# VCO-Simple-Middle.net
KiCad netlist of a schematic drawn in EAGLE
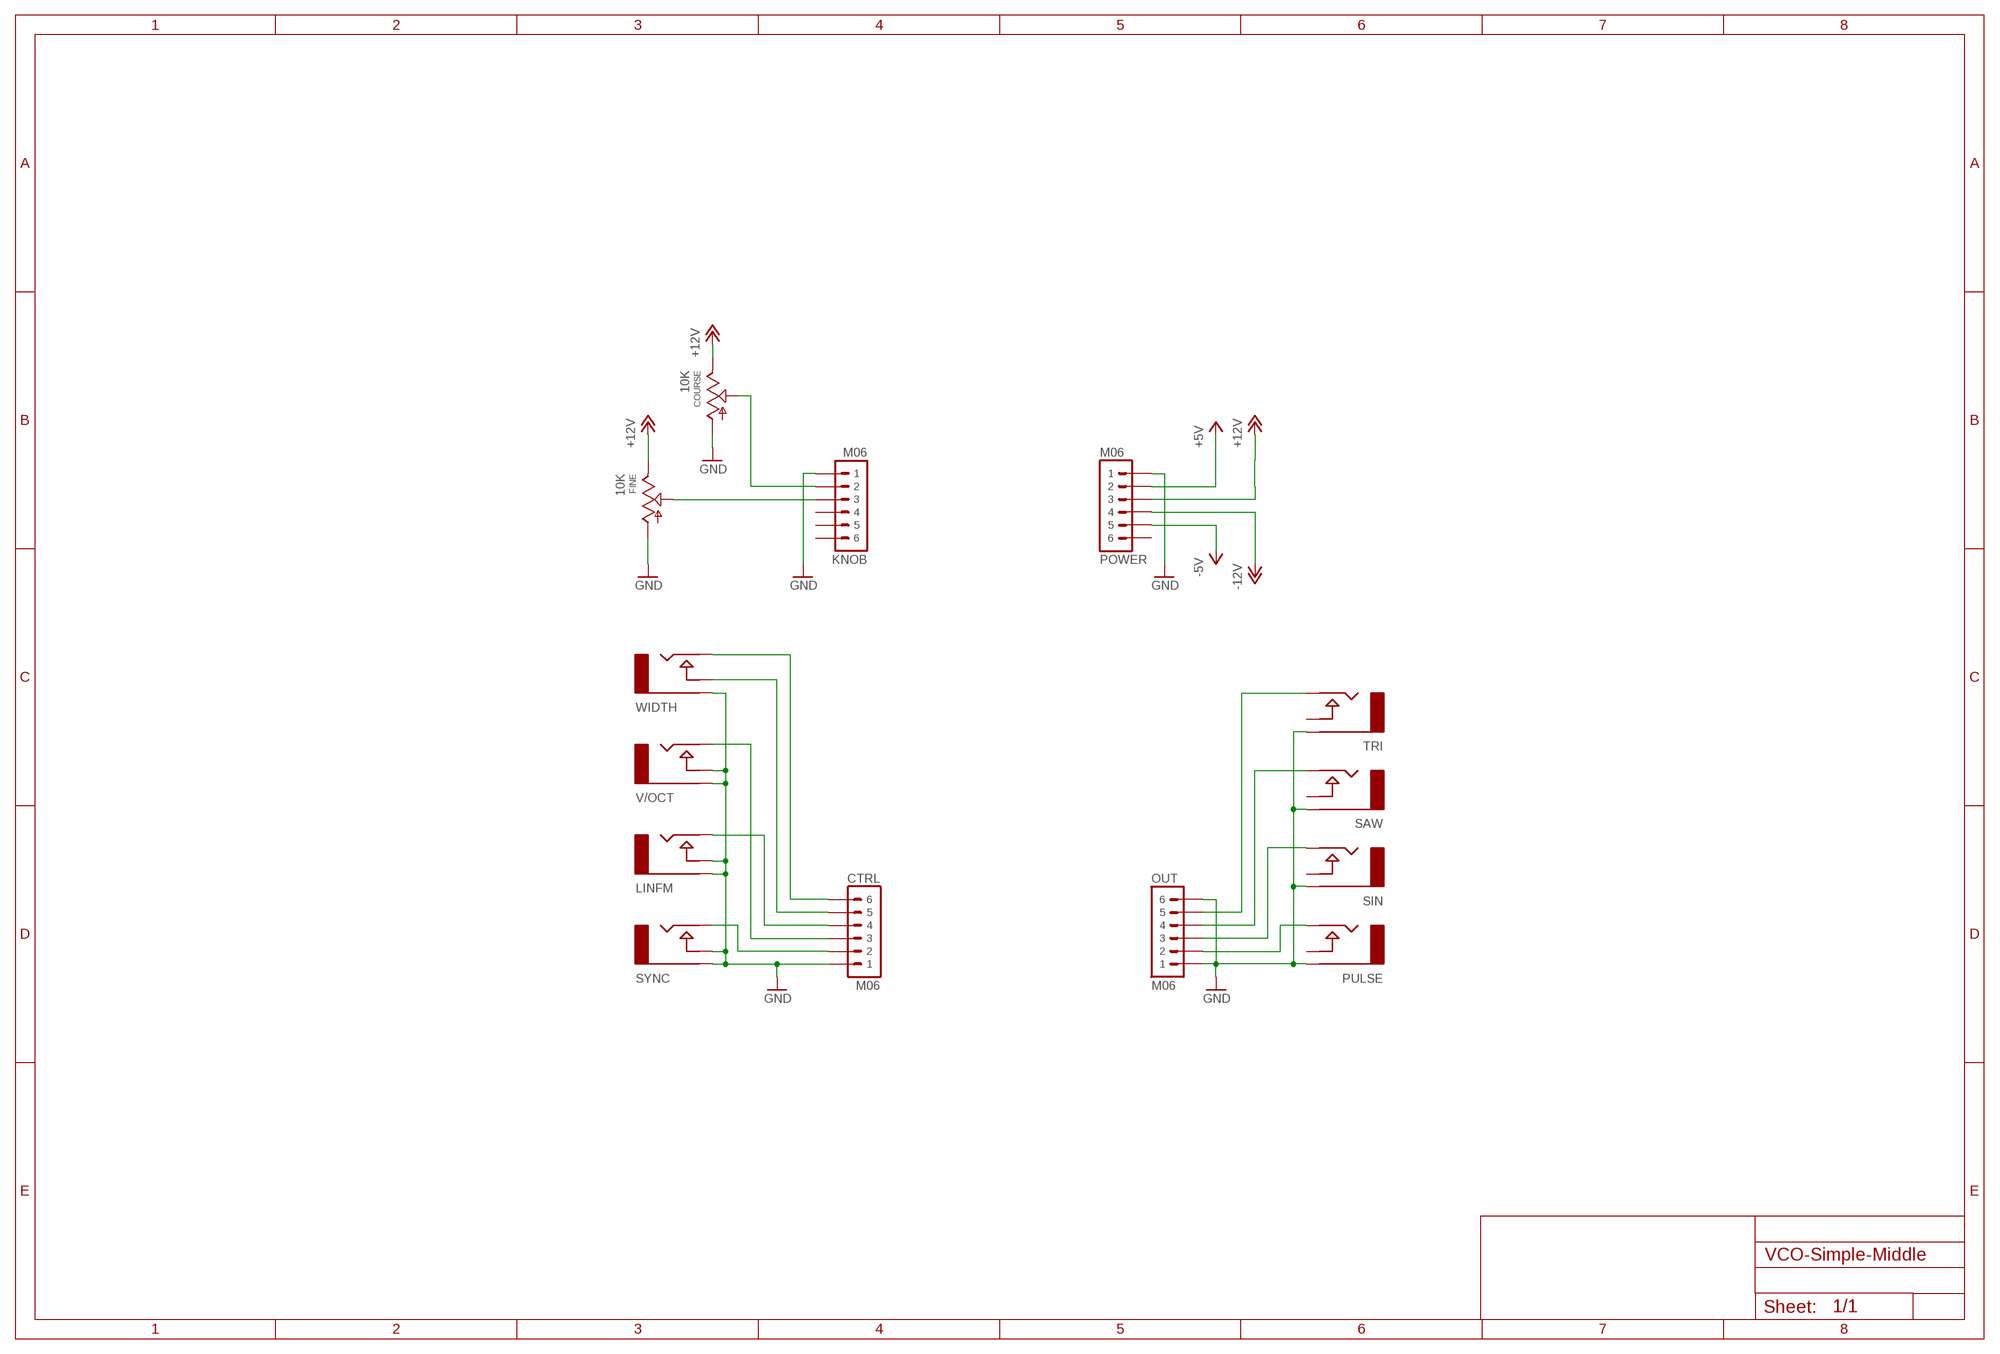
[diagram p0: schematic, sheet 1]

(export (version "E")
  (design (tool "Eeschema 10.0.6"))
  (components
    (comp (ref "COURSE")
      (value "10K")
      (footprint "eagle-import:POT-ALPHA-9MM")
      (libsource (lib "eagle-import") (part "POTALPHA-9MM"))
    )
    (comp (ref "CTRL")
      (value "M06")
      (footprint "eagle-import:M06")
      (libsource (lib "eagle-import") (part "M06"))
    )
    (comp (ref "FINE")
      (value "10K")
      (footprint "eagle-import:POT-ALPHA-9MM")
      (libsource (lib "eagle-import") (part "POTALPHA-9MM"))
    )
    (comp (ref "KNOB")
      (value "M06")
      (footprint "eagle-import:M06")
      (libsource (lib "eagle-import") (part "M06"))
    )
    (comp (ref "LINFM")
      (value "AUDIO-JACKINLINE")
      (footprint "eagle-import:ERTHENVAR-JACK-INLINE")
      (libsource (lib "eagle-import") (part "AUDIO-JACKINLINE"))
    )
    (comp (ref "OUT")
      (value "M06")
      (footprint "eagle-import:M06")
      (libsource (lib "eagle-import") (part "M06"))
    )
    (comp (ref "POWER")
      (value "M06")
      (footprint "eagle-import:M06")
      (libsource (lib "eagle-import") (part "M06"))
    )
    (comp (ref "PULSE")
      (value "AUDIO-JACKINLINE")
      (footprint "eagle-import:ERTHENVAR-JACK-INLINE")
      (libsource (lib "eagle-import") (part "AUDIO-JACKINLINE"))
    )
    (comp (ref "SAW")
      (value "AUDIO-JACKINLINE")
      (footprint "eagle-import:ERTHENVAR-JACK-INLINE")
      (libsource (lib "eagle-import") (part "AUDIO-JACKINLINE"))
    )
    (comp (ref "SIN")
      (value "AUDIO-JACKINLINE")
      (footprint "eagle-import:ERTHENVAR-JACK-INLINE")
      (libsource (lib "eagle-import") (part "AUDIO-JACKINLINE"))
    )
    (comp (ref "SYNC")
      (value "AUDIO-JACKINLINE")
      (footprint "eagle-import:ERTHENVAR-JACK-INLINE")
      (libsource (lib "eagle-import") (part "AUDIO-JACKINLINE"))
    )
    (comp (ref "TRI")
      (value "AUDIO-JACKINLINE")
      (footprint "eagle-import:ERTHENVAR-JACK-INLINE")
      (libsource (lib "eagle-import") (part "AUDIO-JACKINLINE"))
    )
    (comp (ref "V/OCT")
      (value "AUDIO-JACKINLINE")
      (footprint "eagle-import:ERTHENVAR-JACK-INLINE")
      (libsource (lib "eagle-import") (part "AUDIO-JACKINLINE"))
    )
    (comp (ref "WIDTH")
      (value "AUDIO-JACKINLINE")
      (footprint "eagle-import:ERTHENVAR-JACK-INLINE")
      (libsource (lib "eagle-import") (part "AUDIO-JACKINLINE"))
    )
  )
  (nets
    (net (code "1") (name "+5V") (class "Default")
      (node (ref "POWER") (pin "2") (pinfunction "2_2") (pintype "passive"))
    )
    (net (code "2") (name "+12V") (class "Default")
      (node (ref "COURSE") (pin "B") (pinfunction "E_B") (pintype "passive"))
      (node (ref "FINE") (pin "B") (pinfunction "E_B") (pintype "passive"))
      (node (ref "POWER") (pin "3") (pinfunction "3_3") (pintype "passive"))
    )
    (net (code "3") (name "-5V") (class "Default")
      (node (ref "POWER") (pin "5") (pinfunction "5_5") (pintype "passive"))
    )
    (net (code "4") (name "-12V") (class "Default")
      (node (ref "POWER") (pin "4") (pinfunction "4_4") (pintype "passive"))
    )
    (net (code "5") (name "GND") (class "Default")
      (node (ref "COURSE") (pin "A") (pinfunction "A_A") (pintype "passive"))
      (node (ref "CTRL") (pin "1") (pinfunction "1_1") (pintype "passive"))
      (node (ref "FINE") (pin "A") (pinfunction "A_A") (pintype "passive"))
      (node (ref "KNOB") (pin "1") (pinfunction "1_1") (pintype "passive"))
      (node (ref "LINFM") (pin "G") (pinfunction "RING_G") (pintype "bidirectional"))
      (node (ref "LINFM") (pin "N") (pinfunction "NORM_N") (pintype "bidirectional"))
      (node (ref "OUT") (pin "1") (pinfunction "1_1") (pintype "passive"))
      (node (ref "OUT") (pin "6") (pinfunction "6_6") (pintype "passive"))
      (node (ref "POWER") (pin "1") (pinfunction "1_1") (pintype "passive"))
      (node (ref "PULSE") (pin "G") (pinfunction "RING_G") (pintype "bidirectional"))
      (node (ref "SAW") (pin "G") (pinfunction "RING_G") (pintype "bidirectional"))
      (node (ref "SIN") (pin "G") (pinfunction "RING_G") (pintype "bidirectional"))
      (node (ref "SYNC") (pin "G") (pinfunction "RING_G") (pintype "bidirectional"))
      (node (ref "SYNC") (pin "N") (pinfunction "NORM_N") (pintype "bidirectional"))
      (node (ref "TRI") (pin "G") (pinfunction "RING_G") (pintype "bidirectional"))
      (node (ref "V/OCT") (pin "G") (pinfunction "RING_G") (pintype "bidirectional"))
      (node (ref "V/OCT") (pin "N") (pinfunction "NORM_N") (pintype "bidirectional"))
      (node (ref "WIDTH") (pin "G") (pinfunction "RING_G") (pintype "bidirectional"))
    )
    (net (code "6") (name "Net-(COURSE-S)") (class "Default")
      (node (ref "COURSE") (pin "W") (pinfunction "S_W") (pintype "passive"))
      (node (ref "KNOB") (pin "2") (pinfunction "2_2") (pintype "passive"))
    )
    (net (code "7") (name "Net-(FINE-S)") (class "Default")
      (node (ref "FINE") (pin "W") (pinfunction "S_W") (pintype "passive"))
      (node (ref "KNOB") (pin "3") (pinfunction "3_3") (pintype "passive"))
    )
    (net (code "8") (name "Net-(LINFM-TIP)") (class "Default")
      (node (ref "CTRL") (pin "4") (pinfunction "4_4") (pintype "passive"))
      (node (ref "LINFM") (pin "T") (pinfunction "TIP_T") (pintype "bidirectional"))
    )
    (net (code "9") (name "Net-(PULSE-TIP)") (class "Default")
      (node (ref "OUT") (pin "2") (pinfunction "2_2") (pintype "passive"))
      (node (ref "PULSE") (pin "T") (pinfunction "TIP_T") (pintype "bidirectional"))
    )
    (net (code "10") (name "Net-(SAW-TIP)") (class "Default")
      (node (ref "OUT") (pin "4") (pinfunction "4_4") (pintype "passive"))
      (node (ref "SAW") (pin "T") (pinfunction "TIP_T") (pintype "bidirectional"))
    )
    (net (code "11") (name "Net-(SIN-TIP)") (class "Default")
      (node (ref "OUT") (pin "3") (pinfunction "3_3") (pintype "passive"))
      (node (ref "SIN") (pin "T") (pinfunction "TIP_T") (pintype "bidirectional"))
    )
    (net (code "12") (name "Net-(SYNC-TIP)") (class "Default")
      (node (ref "CTRL") (pin "2") (pinfunction "2_2") (pintype "passive"))
      (node (ref "SYNC") (pin "T") (pinfunction "TIP_T") (pintype "bidirectional"))
    )
    (net (code "13") (name "Net-(TRI-TIP)") (class "Default")
      (node (ref "OUT") (pin "5") (pinfunction "5_5") (pintype "passive"))
      (node (ref "TRI") (pin "T") (pinfunction "TIP_T") (pintype "bidirectional"))
    )
    (net (code "14") (name "Net-(V/OCT-TIP)") (class "Default")
      (node (ref "CTRL") (pin "3") (pinfunction "3_3") (pintype "passive"))
      (node (ref "V/OCT") (pin "T") (pinfunction "TIP_T") (pintype "bidirectional"))
    )
    (net (code "15") (name "Net-(WIDTH-NORM)") (class "Default")
      (node (ref "CTRL") (pin "5") (pinfunction "5_5") (pintype "passive"))
      (node (ref "WIDTH") (pin "N") (pinfunction "NORM_N") (pintype "bidirectional"))
    )
    (net (code "16") (name "Net-(WIDTH-TIP)") (class "Default")
      (node (ref "CTRL") (pin "6") (pinfunction "6_6") (pintype "passive"))
      (node (ref "WIDTH") (pin "T") (pinfunction "TIP_T") (pintype "bidirectional"))
    )
    (net (code "17") (name "unconnected-(KNOB-Pad4)") (class "Default")
      (node (ref "KNOB") (pin "4") (pinfunction "4_4") (pintype "passive"))
    )
    (net (code "18") (name "unconnected-(KNOB-Pad5)") (class "Default")
      (node (ref "KNOB") (pin "5") (pinfunction "5_5") (pintype "passive"))
    )
    (net (code "19") (name "unconnected-(KNOB-Pad6)") (class "Default")
      (node (ref "KNOB") (pin "6") (pinfunction "6_6") (pintype "passive"))
    )
    (net (code "20") (name "unconnected-(POWER-Pad6)") (class "Default")
      (node (ref "POWER") (pin "6") (pinfunction "6_6") (pintype "passive"))
    )
    (net (code "21") (name "unconnected-(PULSE-NORM-PadN)") (class "Default")
      (node (ref "PULSE") (pin "N") (pinfunction "NORM_N") (pintype "bidirectional"))
    )
    (net (code "22") (name "unconnected-(SAW-NORM-PadN)") (class "Default")
      (node (ref "SAW") (pin "N") (pinfunction "NORM_N") (pintype "bidirectional"))
    )
    (net (code "23") (name "unconnected-(SIN-NORM-PadN)") (class "Default")
      (node (ref "SIN") (pin "N") (pinfunction "NORM_N") (pintype "bidirectional"))
    )
    (net (code "24") (name "unconnected-(TRI-NORM-PadN)") (class "Default")
      (node (ref "TRI") (pin "N") (pinfunction "NORM_N") (pintype "bidirectional"))
    )
  )
)
